# ON_OFF_Controller.net
KiCad netlist of a schematic drawn in Altium Designer
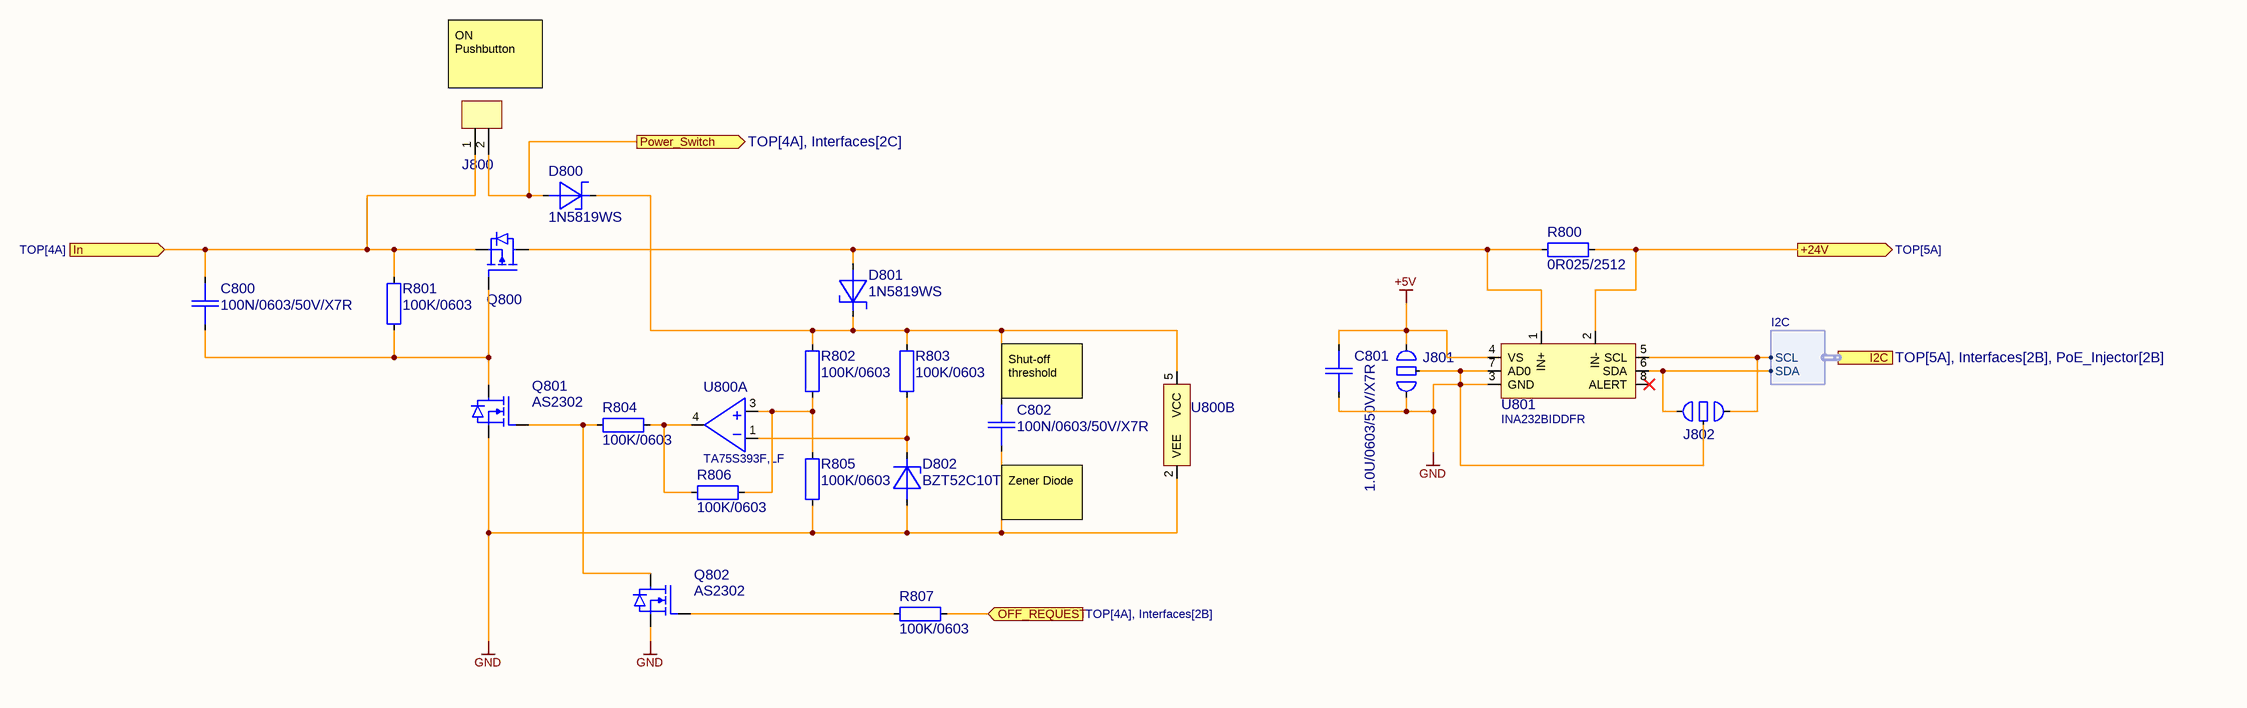
[diagram p0: ON_OFF_Controller.SchDoc]

(export (version "E")
  (design (tool "Eeschema 10.0.6"))
  (components
    (comp (ref "C800")
      (value "100N/0603/50V/X7R")
      (footprint "CAP0603_X7R")
      (description "CAP SM 0603 100nF 50V X7R")
      (fields (field (name "MANUFACTURER") "GENERIC"))
      (libsource (lib "daniw_altium_lib") (part "C"))
    )
    (comp (ref "C801")
      (value "1.0U/0603/50V/X7R")
      (footprint "CAP0603_X7R")
      (description "CAP SM 0603 1.0uF 50V X7R")
      (fields (field (name "MANUFACTURER") "GENERIC"))
      (libsource (lib "daniw_altium_lib") (part "C"))
    )
    (comp (ref "C802")
      (value "100N/0603/50V/X7R")
      (footprint "CAP0603_X7R")
      (description "CAP SM 0603 100nF 50V X7R")
      (fields (field (name "MANUFACTURER") "GENERIC"))
      (libsource (lib "daniw_altium_lib") (part "C"))
    )
    (comp (ref "D800")
      (value "1N5819WS")
      (footprint "SOD2513X100")
      (description "40V 600mV@1A 1A SOD-323 Schottky Barrier Diodes (SBD) ROHS")
      (fields (field (name "MANUFACTURER") "GENERIC"))
      (libsource (lib "daniw_altium_lib") (part "D_Schottky"))
    )
    (comp (ref "D801")
      (value "1N5819WS")
      (footprint "SOD2513X100")
      (description "40V 600mV@1A 1A SOD-323 Schottky Barrier Diodes (SBD) ROHS")
      (fields (field (name "MANUFACTURER") "GENERIC"))
      (libsource (lib "daniw_altium_lib") (part "D_Schottky"))
    )
    (comp (ref "D802")
      (value "BZT52C10T")
      (footprint "SOD1608X065")
      (description "DIODE ZENER 10V 100MW SOD523")
      (fields (field (name "MANUFACTURER") "Micro Commercial Co"))
      (libsource (lib "daniw_altium_lib") (part "D_Zener"))
    )
    (comp (ref "J800")
      (value "430450212")
      (footprint "430450212")
      (fields (field (name "PART NUMBER") "Microfit_3.0_1x2_VERT_THT"))
      (libsource (lib "daniw_altium_lib") (part "CON2"))
    )
    (comp (ref "J801")
      (value "Solder Jumper 3pin 0.2mm")
      (footprint "Solder_Jumper_3pin_0.2mm")
      (description "Solder jumper with three pins with a spacing of 0.2mm")
      (fields (field (name "PART NUMBER") "Solder_Jumper_3pin_0.2mm") (field (name "MANUFACTURER") "NONE"))
      (libsource (lib "daniw_altium_lib") (part "SolderJumper_3"))
    )
    (comp (ref "J802")
      (value "Solder Jumper 3pin 0.2mm")
      (footprint "Solder_Jumper_3pin_0.2mm")
      (description "Solder jumper with three pins with a spacing of 0.2mm")
      (fields (field (name "PART NUMBER") "Solder_Jumper_3pin_0.2mm") (field (name "MANUFACTURER") "NONE"))
      (libsource (lib "daniw_altium_lib") (part "SolderJumper_3"))
    )
    (comp (ref "Q800")
      (value "MCG35P04-TP")
      (footprint "SON065P330X330X075-5-TH245X175")
      (description "40V 35A P-Channel MOSFET")
      (fields (field (name "MANUFACTURER") "Micro Commercial Co"))
      (libsource (lib "daniw_altium_lib") (part "MOSFET P"))
    )
    (comp (ref "Q801")
      (value "AS2302")
      (footprint "SOT2395P280X125-3-SE")
      (description "N-Channel 20V(D-S) MOSFET")
      (fields (field (name "MANUFACTURER") "GENERIC"))
      (libsource (lib "daniw_altium_lib") (part "MOSFET N_SOT23"))
    )
    (comp (ref "Q802")
      (value "AS2302")
      (footprint "SOT2395P280X125-3-SE")
      (description "N-Channel 20V(D-S) MOSFET")
      (fields (field (name "MANUFACTURER") "GENERIC"))
      (libsource (lib "daniw_altium_lib") (part "MOSFET N_SOT23"))
    )
    (comp (ref "R800")
      (value "0R025/2512")
      (footprint "R2512-0.65-WW")
      (description "RES SM 2512 0R025")
      (fields (field (name "MANUFACTURER") "GENERIC"))
      (libsource (lib "daniw_altium_lib") (part "R"))
    )
    (comp (ref "R801")
      (value "100K/0603")
      (footprint "R0603-0.40-WW")
      (description "RES SM 0603 100K")
      (fields (field (name "MANUFACTURER") "GENERIC"))
      (libsource (lib "daniw_altium_lib") (part "R"))
    )
    (comp (ref "R802")
      (value "100K/0603")
      (footprint "R0603-0.40-WW")
      (description "RES SM 0603 100K")
      (fields (field (name "MANUFACTURER") "GENERIC"))
      (libsource (lib "daniw_altium_lib") (part "R"))
    )
    (comp (ref "R803")
      (value "100K/0603")
      (footprint "R0603-0.40-WW")
      (description "RES SM 0603 100K")
      (fields (field (name "MANUFACTURER") "GENERIC"))
      (libsource (lib "daniw_altium_lib") (part "R"))
    )
    (comp (ref "R804")
      (value "100K/0603")
      (footprint "R0603-0.40-WW")
      (description "RES SM 0603 100K")
      (fields (field (name "MANUFACTURER") "GENERIC"))
      (libsource (lib "daniw_altium_lib") (part "R"))
    )
    (comp (ref "R805")
      (value "100K/0603")
      (footprint "R0603-0.40-WW")
      (description "RES SM 0603 100K")
      (fields (field (name "MANUFACTURER") "GENERIC"))
      (libsource (lib "daniw_altium_lib") (part "R"))
    )
    (comp (ref "R806")
      (value "100K/0603")
      (footprint "R0603-0.40-WW")
      (description "RES SM 0603 100K")
      (fields (field (name "MANUFACTURER") "GENERIC"))
      (libsource (lib "daniw_altium_lib") (part "R"))
    )
    (comp (ref "R807")
      (value "100K/0603")
      (footprint "R0603-0.40-WW")
      (description "RES SM 0603 100K")
      (fields (field (name "MANUFACTURER") "GENERIC"))
      (libsource (lib "daniw_altium_lib") (part "R"))
    )
    (comp (ref "U800")
      (value "TA75S393F,LF")
      (footprint "SOT2395P280X125-5-SW")
      (description "36V Single Voltage Comparator")
      (fields (field (name "MANUFACTURER") "Toshiba Semiconductor and Storage"))
      (libsource (lib "") (part "OPA_SOT23_1"))
    )
    (comp (ref "U801")
      (value "INA232BIDDFR")
      (footprint "SOT065P280X110-8-SE")
      (description "INA232 48-V, 16-Bit, Current, Voltage, and Power Monitor With an I2C Interface")
      (fields (field (name "MANUFACTURER") "Texas Instruments"))
      (libsource (lib "daniw_altium_lib") (part "INA232"))
    )
  )
  (nets
    (net (code "2") (name "+5V") (class "Default")
      (node (ref "C801") (pin "1") (pinfunction "1_1") (pintype "passive"))
      (node (ref "J801") (pin "3") (pinfunction "3_3") (pintype "passive"))
      (node (ref "U801") (pin "4") (pinfunction "VS_4") (pintype "passive"))
    )
    (net (code "3") (name "/+24V") (class "Default")
      (node (ref "R800") (pin "2") (pinfunction "2_2") (pintype "passive"))
      (node (ref "U801") (pin "2") (pinfunction "IN-_2") (pintype "passive"))
    )
    (net (code "4") (name "/In") (class "Default")
      (node (ref "C800") (pin "1") (pinfunction "1_1") (pintype "passive"))
      (node (ref "J800") (pin "1") (pintype "passive"))
      (node (ref "Q800") (pin "S") (pinfunction "SOURCE_S") (pintype "passive"))
      (node (ref "R801") (pin "1") (pinfunction "1_1") (pintype "passive"))
    )
    (net (code "5") (name "/OFF_REQUEST") (class "Default")
      (node (ref "R807") (pin "1") (pinfunction "1_1") (pintype "passive"))
    )
    (net (code "6") (name "/Power_Switch") (class "Default")
      (node (ref "D800") (pin "2") (pinfunction "2_2") (pintype "passive"))
      (node (ref "J800") (pin "2") (pintype "passive"))
    )
    (net (code "8") (name "GND") (class "Default")
      (node (ref "C801") (pin "2") (pinfunction "2_2") (pintype "passive"))
      (node (ref "C802") (pin "2") (pinfunction "2_2") (pintype "passive"))
      (node (ref "D802") (pin "2") (pinfunction "2_2") (pintype "passive"))
      (node (ref "J801") (pin "1") (pinfunction "1_1") (pintype "passive"))
      (node (ref "J801") (pin "2") (pinfunction "2_2") (pintype "passive"))
      (node (ref "J802") (pin "2") (pinfunction "2_2") (pintype "passive"))
      (node (ref "Q801") (pin "2") (pinfunction "SOURCE_2") (pintype "passive"))
      (node (ref "Q802") (pin "2") (pinfunction "SOURCE_2") (pintype "passive"))
      (node (ref "R805") (pin "2") (pinfunction "2_2") (pintype "passive"))
      (node (ref "U800") (pin "2") (pinfunction "VEE_2") (pintype "passive"))
      (node (ref "U801") (pin "3") (pinfunction "GND_3") (pintype "passive"))
      (node (ref "U801") (pin "7") (pinfunction "AD0_7") (pintype "passive"))
    )
    (net (code "9") (name "Net-(Q800-DRAIN)") (class "Default")
      (node (ref "D801") (pin "2") (pinfunction "2_2") (pintype "passive"))
      (node (ref "Q800") (pin "D") (pinfunction "DRAIN_D") (pintype "passive"))
      (node (ref "R800") (pin "1") (pinfunction "1_1") (pintype "passive"))
      (node (ref "U801") (pin "1") (pinfunction "IN+_1") (pintype "passive"))
    )
    (net (code "10") (name "Net-(Q800-GATE)") (class "Default")
      (node (ref "C800") (pin "2") (pinfunction "2_2") (pintype "passive"))
      (node (ref "Q800") (pin "G") (pinfunction "GATE_G") (pintype "passive"))
      (node (ref "Q801") (pin "3") (pinfunction "DRAIN_3") (pintype "passive"))
      (node (ref "R801") (pin "2") (pinfunction "2_2") (pintype "passive"))
    )
    (net (code "11") (name "Net-(Q801-GATE)") (class "Default")
      (node (ref "Q801") (pin "1") (pinfunction "GATE_1") (pintype "passive"))
      (node (ref "Q802") (pin "3") (pinfunction "DRAIN_3") (pintype "passive"))
      (node (ref "R804") (pin "1") (pinfunction "1_1") (pintype "passive"))
    )
    (net (code "12") (name "Net-(Q802-GATE)") (class "Default")
      (node (ref "Q802") (pin "1") (pinfunction "GATE_1") (pintype "passive"))
      (node (ref "R807") (pin "2") (pinfunction "2_2") (pintype "passive"))
    )
    (net (code "13") (name "Net-(U800A-IN+)") (class "Default")
      (node (ref "R802") (pin "2") (pinfunction "2_2") (pintype "passive"))
      (node (ref "R805") (pin "1") (pinfunction "1_1") (pintype "passive"))
      (node (ref "R806") (pin "1") (pinfunction "1_1") (pintype "passive"))
      (node (ref "U800") (pin "3") (pinfunction "IN+_3") (pintype "passive"))
    )
    (net (code "14") (name "Net-(U800A-IN-)") (class "Default")
      (node (ref "D802") (pin "1") (pinfunction "1_1") (pintype "passive"))
      (node (ref "R803") (pin "2") (pinfunction "2_2") (pintype "passive"))
      (node (ref "U800") (pin "1") (pinfunction "IN-_1") (pintype "passive"))
    )
    (net (code "15") (name "Net-(U800A-OUT)") (class "Default")
      (node (ref "R804") (pin "2") (pinfunction "2_2") (pintype "passive"))
      (node (ref "R806") (pin "2") (pinfunction "2_2") (pintype "passive"))
      (node (ref "U800") (pin "4") (pinfunction "OUT_4") (pintype "passive"))
    )
    (net (code "16") (name "Net-(U800B-VCC)") (class "Default")
      (node (ref "C802") (pin "1") (pinfunction "1_1") (pintype "passive"))
      (node (ref "D800") (pin "1") (pinfunction "1_1") (pintype "passive"))
      (node (ref "D801") (pin "1") (pinfunction "1_1") (pintype "passive"))
      (node (ref "R802") (pin "1") (pinfunction "1_1") (pintype "passive"))
      (node (ref "R803") (pin "1") (pinfunction "1_1") (pintype "passive"))
      (node (ref "U800") (pin "5") (pinfunction "VCC_5") (pintype "passive"))
    )
    (net (code "17") (name "Net-(U801-SCL)") (class "Default")
      (node (ref "J802") (pin "3") (pinfunction "3_3") (pintype "passive"))
      (node (ref "U801") (pin "5") (pinfunction "SCL_5") (pintype "passive"))
    )
    (net (code "18") (name "Net-(U801-SDA)") (class "Default")
      (node (ref "J802") (pin "1") (pinfunction "1_1") (pintype "passive"))
      (node (ref "U801") (pin "6") (pinfunction "SDA_6") (pintype "passive"))
    )
    (net (code "19") (name "unconnected-(U801-ALERT-Pad8)") (class "Default")
      (node (ref "U801") (pin "8") (pinfunction "ALERT_8") (pintype "passive+no_connect"))
    )
  )
)
